# iNodeSwitch_v0_1.net
KiCad netlist of a schematic drawn in EAGLE
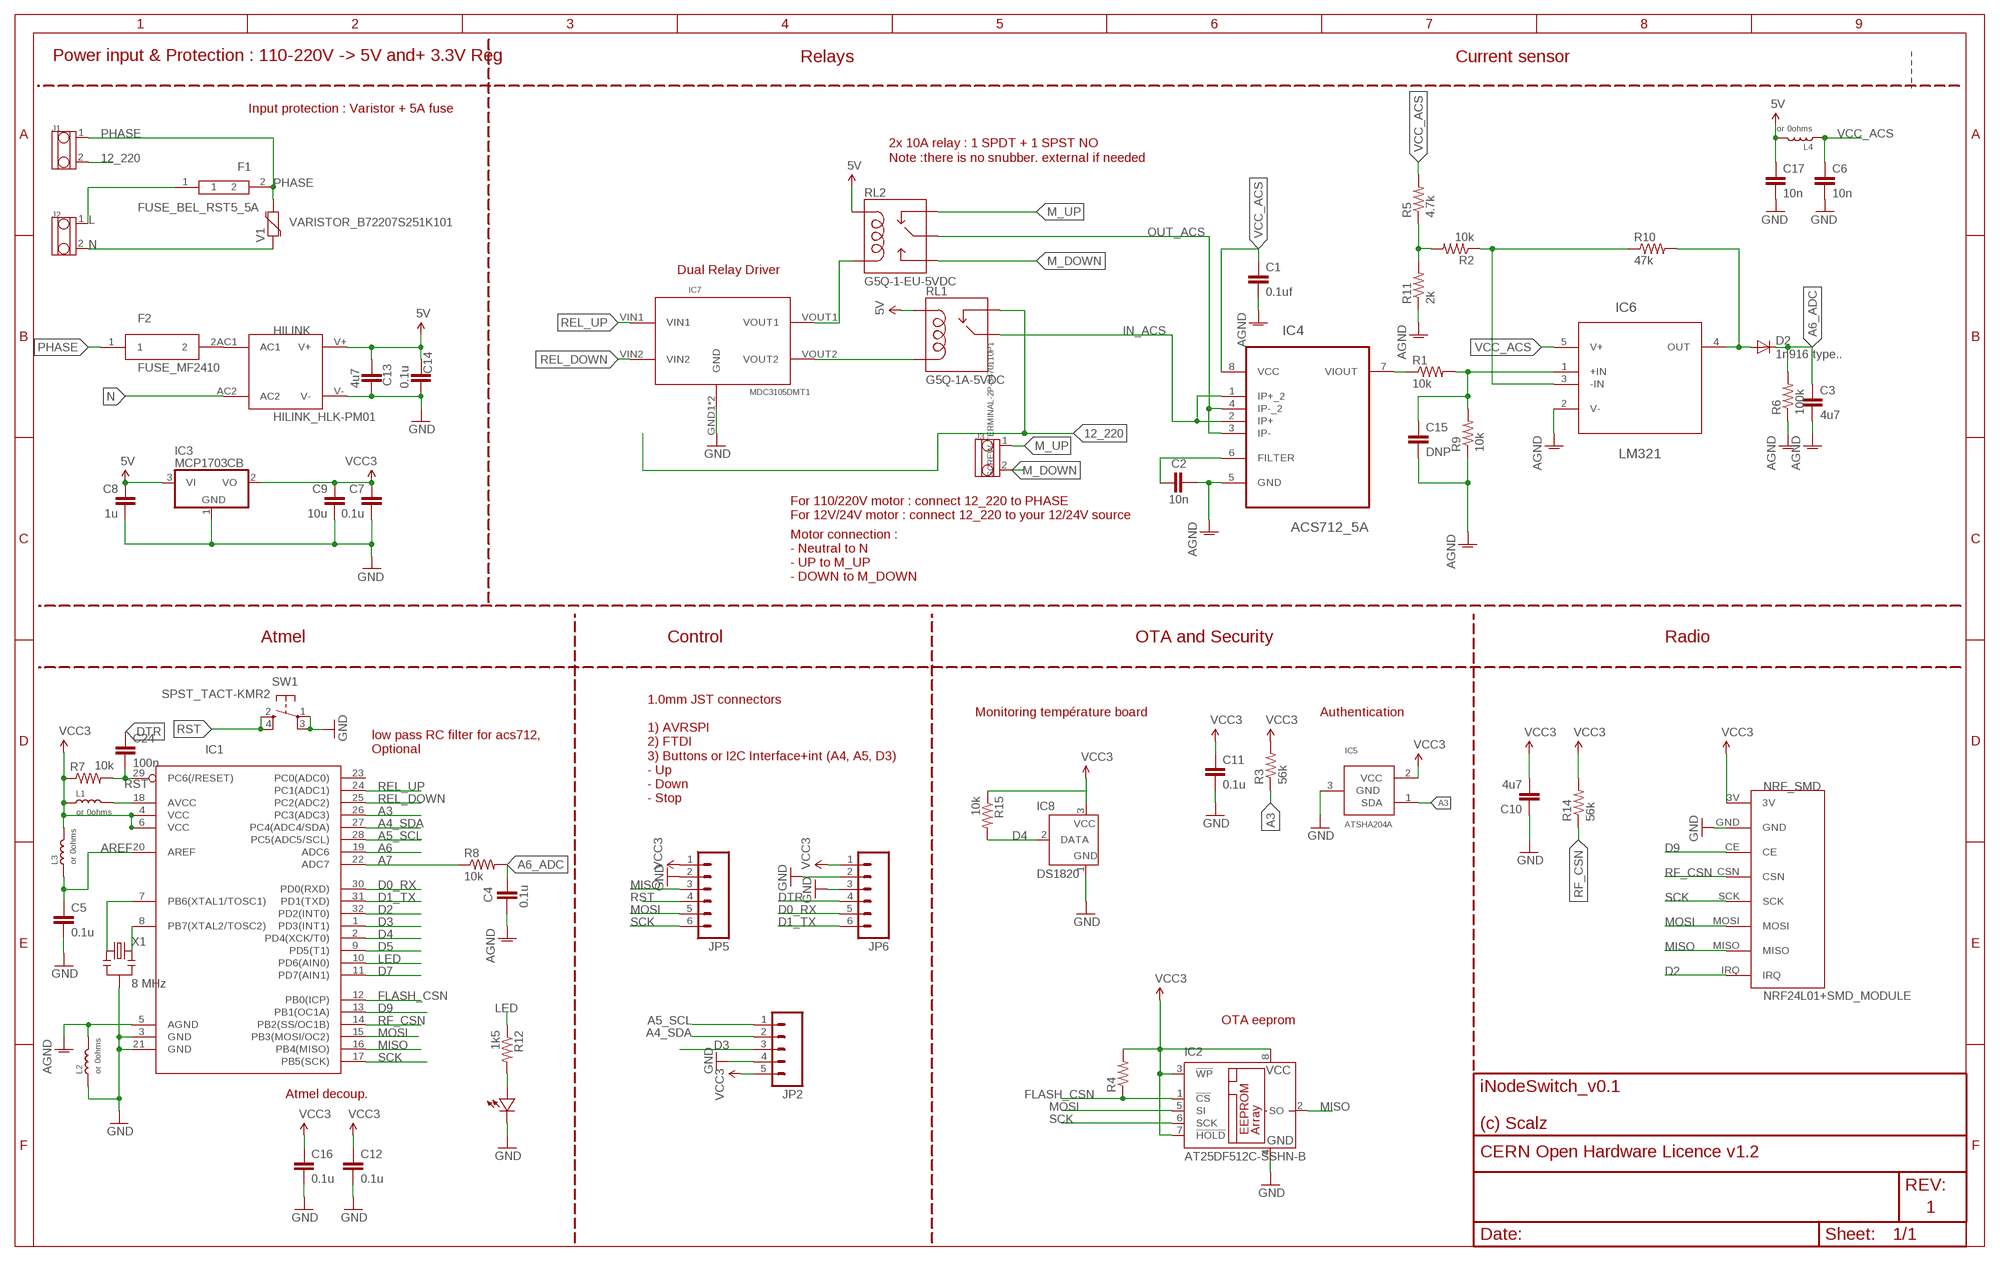
[diagram p0: schematic, sheet 1]

(export (version "E")
  (design (tool "Eeschema 10.0.6"))
  (components
    (comp (ref "C1")
      (value "0.1uf")
      (footprint "eagle-import:0805-CAP")
      (libsource (lib "eagle-import") (part "CAP0805-CAP"))
    )
    (comp (ref "C2")
      (value "10n")
      (footprint "eagle-import:0805-CAP")
      (libsource (lib "eagle-import") (part "CAP0805-CAP"))
    )
    (comp (ref "C3")
      (value "4u7")
      (footprint "eagle-import:0805-CAP")
      (libsource (lib "eagle-import") (part "CAP0805-CAP"))
    )
    (comp (ref "C4")
      (value "0.1u")
      (footprint "eagle-import:0805-CAP")
      (libsource (lib "eagle-import") (part "CAP0805-CAP"))
    )
    (comp (ref "C5")
      (value "0.1u")
      (footprint "eagle-import:0805-CAP")
      (libsource (lib "eagle-import") (part "CAP0805-CAP"))
    )
    (comp (ref "C6")
      (value "10n")
      (footprint "eagle-import:0805-CAP")
      (libsource (lib "eagle-import") (part "CAP0805-CAP"))
    )
    (comp (ref "C7")
      (value "0.1u")
      (footprint "eagle-import:0805-CAP")
      (libsource (lib "eagle-import") (part "CAP0805-CAP"))
    )
    (comp (ref "C8")
      (value "1u")
      (footprint "eagle-import:0805-CAP")
      (libsource (lib "eagle-import") (part "CAP0805-CAP"))
    )
    (comp (ref "C9")
      (value "10u")
      (footprint "eagle-import:0805-CAP")
      (libsource (lib "eagle-import") (part "CAP0805-CAP"))
    )
    (comp (ref "C10")
      (value "4u7")
      (footprint "eagle-import:0805-CAP")
      (libsource (lib "eagle-import") (part "CAP0805-CAP"))
    )
    (comp (ref "C11")
      (value "0.1u")
      (footprint "eagle-import:0805-CAP")
      (libsource (lib "eagle-import") (part "CAP0805-CAP"))
    )
    (comp (ref "C12")
      (value "0.1u")
      (footprint "eagle-import:0805-CAP")
      (libsource (lib "eagle-import") (part "CAP0805-CAP"))
    )
    (comp (ref "C13")
      (value "4u7")
      (footprint "eagle-import:0805-CAP")
      (libsource (lib "eagle-import") (part "CAP0805-CAP"))
    )
    (comp (ref "C14")
      (value "0.1u")
      (footprint "eagle-import:0805-CAP")
      (libsource (lib "eagle-import") (part "CAP0805-CAP"))
    )
    (comp (ref "C15")
      (value "DNP")
      (footprint "eagle-import:0805-CAP")
      (libsource (lib "eagle-import") (part "CAP0805-CAP"))
    )
    (comp (ref "C16")
      (value "0.1u")
      (footprint "eagle-import:0805-CAP")
      (libsource (lib "eagle-import") (part "CAP0805-CAP"))
    )
    (comp (ref "C17")
      (value "10n")
      (footprint "eagle-import:0805-CAP")
      (libsource (lib "eagle-import") (part "CAP0805-CAP"))
    )
    (comp (ref "C24")
      (value "100n")
      (footprint "eagle-import:0805-CAP")
      (libsource (lib "eagle-import") (part "CAP0805-CAP"))
    )
    (comp (ref "D1")
      (value "LED0805")
      (footprint "eagle-import:0805-LED")
      (libsource (lib "eagle-import") (part "LED0805"))
    )
    (comp (ref "D2")
      (value "1n916 type..")
      (footprint "eagle-import:SOD-323")
      (libsource (lib "eagle-import") (part "DIODESOD"))
    )
    (comp (ref "F1")
      (value "FUSE_BEL_RST5_5A")
      (footprint "eagle-import:FUSE_BEL_RST5_5A")
      (libsource (lib "eagle-import") (part "FUSE_BEL_RST5_5A"))
    )
    (comp (ref "F2")
      (value "FUSE_MF2410")
      (footprint "eagle-import:2410")
      (libsource (lib "eagle-import") (part "FUSE_MF2410"))
    )
    (comp (ref "HILINK")
      (value "HILINK_HLK-PM01")
      (footprint "eagle-import:HILINK_HLK-PM01")
      (libsource (lib "eagle-import") (part "HILINK_HLK-PM01"))
    )
    (comp (ref "IC1")
      (value "ATMega-328")
      (footprint "eagle-import:TQFP32-08")
      (libsource (lib "eagle-import") (part "ATMEGA168/328TQFP32"))
    )
    (comp (ref "IC2")
      (value "AT25DF512C-SSHN-B")
      (footprint "eagle-import:SO-08")
      (fields (field (name "MF") "MICROCHIP") (field (name "MPN") "25AA080/SN"))
      (libsource (lib "eagle-import") (part "25SNAA080"))
    )
    (comp (ref "IC3")
      (value "MCP1703CB")
      (footprint "eagle-import:SOT23")
      (libsource (lib "eagle-import") (part "MCP1703CB"))
    )
    (comp (ref "IC4")
      (value "ACS712_5A")
      (footprint "eagle-import:SOIC127P600X175-8N")
      (fields (field (name "MPN") "ACS712ELCTR-20A-T"))
      (libsource (lib "eagle-import") (part "ACS712ELCTR-20A-T"))
    )
    (comp (ref "IC5")
      (value "ATSHA204A")
      (footprint "eagle-import:SOT23")
      (libsource (lib "eagle-import") (part "ATSHA204A"))
    )
    (comp (ref "IC6")
      (value "LM321")
      (footprint "eagle-import:SOT95P285X120-5N")
      (fields (field (name "MPN") "LM321MF"))
      (libsource (lib "eagle-import") (part "LM321MF"))
    )
    (comp (ref "IC7")
      (value "MDC3105DMT1")
      (footprint "eagle-import:MDC3105DMT1")
      (libsource (lib "eagle-import") (part "MDC3105DMT1"))
    )
    (comp (ref "IC8")
      (value "DS1820")
      (footprint "eagle-import:TO92-")
      (libsource (lib "eagle-import") (part "DS1820"))
    )
    (comp (ref "J1")
      (value "SCREW-TERMINAL-2P-3470110P1")
      (footprint "eagle-import:2P-5.0")
      (libsource (lib "eagle-import") (part "SCREW-TERMINAL-2P-3470110P1"))
    )
    (comp (ref "J2")
      (value "SCREW-TERMINAL-2P-3470110P1")
      (footprint "eagle-import:2P-5.0")
      (libsource (lib "eagle-import") (part "SCREW-TERMINAL-2P-3470110P1"))
    )
    (comp (ref "J3")
      (value "SCREW-TERMINAL-2P-3470110P1")
      (footprint "eagle-import:2P-5.0")
      (libsource (lib "eagle-import") (part "SCREW-TERMINAL-2P-3470110P1"))
    )
    (comp (ref "JP2")
      (value "M05SMD")
      (footprint "eagle-import:1X05-1MM")
      (libsource (lib "eagle-import") (part "M05SMD"))
    )
    (comp (ref "JP5")
      (value "M06SMD-1MM")
      (footprint "eagle-import:1X06-1MM")
      (libsource (lib "eagle-import") (part "M06SMD-1MM"))
    )
    (comp (ref "JP6")
      (value "M06SMD-1MM")
      (footprint "eagle-import:1X06-1MM")
      (libsource (lib "eagle-import") (part "M06SMD-1MM"))
    )
    (comp (ref "L1")
      (value "or 0ohms")
      (footprint "eagle-import:L0805")
      (libsource (lib "eagle-import") (part "INDUCTOR/FERRITE-BEAD-0805"))
    )
    (comp (ref "L2")
      (value "or 0ohms")
      (footprint "eagle-import:L0805")
      (libsource (lib "eagle-import") (part "INDUCTOR/FERRITE-BEAD-0805"))
    )
    (comp (ref "L3")
      (value "or 0ohms")
      (footprint "eagle-import:L0805")
      (libsource (lib "eagle-import") (part "INDUCTOR/FERRITE-BEAD-0805"))
    )
    (comp (ref "L4")
      (value "or 0ohms")
      (footprint "eagle-import:L0805")
      (libsource (lib "eagle-import") (part "INDUCTOR/FERRITE-BEAD-0805"))
    )
    (comp (ref "NRF_SMD")
      (value "NRF24L01+SMD_MODULE")
      (footprint "eagle-import:NRF24L01+SMD_MODULE")
      (libsource (lib "eagle-import") (part "NRF24L01+SMD_MODULE"))
    )
    (comp (ref "R1")
      (value "10k")
      (footprint "eagle-import:0805-RES")
      (libsource (lib "eagle-import") (part "RESISTOR0805-RES"))
    )
    (comp (ref "R2")
      (value "10k")
      (footprint "eagle-import:0805-RES")
      (libsource (lib "eagle-import") (part "RESISTOR0805-RES"))
    )
    (comp (ref "R3")
      (value "56k")
      (footprint "eagle-import:0805-RES")
      (libsource (lib "eagle-import") (part "RESISTOR0805-RES"))
    )
    (comp (ref "R4")
      (value "RESISTOR0805-RES")
      (footprint "eagle-import:0805-RES")
      (libsource (lib "eagle-import") (part "RESISTOR0805-RES"))
    )
    (comp (ref "R5")
      (value "4.7k")
      (footprint "eagle-import:0805-RES")
      (libsource (lib "eagle-import") (part "RESISTOR0805-RES"))
    )
    (comp (ref "R6")
      (value "100k")
      (footprint "eagle-import:0805-RES")
      (libsource (lib "eagle-import") (part "RESISTOR0805-RES"))
    )
    (comp (ref "R7")
      (value "10k")
      (footprint "eagle-import:0805-RES")
      (libsource (lib "eagle-import") (part "RESISTOR0805-RES"))
    )
    (comp (ref "R8")
      (value "10k")
      (footprint "eagle-import:0805-RES")
      (libsource (lib "eagle-import") (part "RESISTOR0805-RES"))
    )
    (comp (ref "R9")
      (value "10k")
      (footprint "eagle-import:0805-RES")
      (libsource (lib "eagle-import") (part "RESISTOR0805-RES"))
    )
    (comp (ref "R10")
      (value "47k")
      (footprint "eagle-import:0805-RES")
      (libsource (lib "eagle-import") (part "RESISTOR0805-RES"))
    )
    (comp (ref "R11")
      (value "2k")
      (footprint "eagle-import:0805-RES")
      (libsource (lib "eagle-import") (part "RESISTOR0805-RES"))
    )
    (comp (ref "R12")
      (value "1k5")
      (footprint "eagle-import:0805-RES")
      (libsource (lib "eagle-import") (part "RESISTOR0805-RES"))
    )
    (comp (ref "R14")
      (value "56k")
      (footprint "eagle-import:0805-RES")
      (libsource (lib "eagle-import") (part "RESISTOR0805-RES"))
    )
    (comp (ref "R15")
      (value "10k")
      (footprint "eagle-import:0805-RES")
      (libsource (lib "eagle-import") (part "RESISTOR0805-RES"))
    )
    (comp (ref "RL1")
      (value "G5Q-1A-5VDC")
      (footprint "eagle-import:G5Q_SINGLE")
      (libsource (lib "eagle-import") (part "G5Q_SINGLE"))
    )
    (comp (ref "RL2")
      (value "G5Q-1-EU-5VDC")
      (footprint "eagle-import:RELAY-G5Q")
      (libsource (lib "eagle-import") (part "RELAYPTH"))
    )
    (comp (ref "SW1")
      (value "SPST_TACT-KMR2")
      (footprint "eagle-import:KMR2")
      (libsource (lib "eagle-import") (part "SPST_TACT-KMR2"))
    )
    (comp (ref "V1")
      (value "VARISTOR_B72207S251K101")
      (footprint "eagle-import:VARISTOR_B72207S251K101")
      (libsource (lib "eagle-import") (part "VARISTOR_B72207S251K101"))
    )
    (comp (ref "X1")
      (value "8 MHz")
      (footprint "eagle-import:RESONATOR-SMD")
      (libsource (lib "eagle-import") (part "RESONATORSMD"))
    )
  )
  (nets
    (net (code "1") (name "/A4_SDA") (class "Default")
      (node (ref "IC1") (pin "27") (pinfunction "PC4(ADC4/SDA)_27") (pintype "bidirectional"))
      (node (ref "JP2") (pin "2") (pinfunction "2_2") (pintype "passive"))
    )
    (net (code "2") (name "/A5_SCL") (class "Default")
      (node (ref "IC1") (pin "28") (pinfunction "PC5(ADC5/SCL)_28") (pintype "bidirectional"))
      (node (ref "JP2") (pin "1") (pinfunction "1_1") (pintype "passive"))
    )
    (net (code "3") (name "/A6") (class "Default")
      (node (ref "IC1") (pin "19") (pinfunction "ADC6_19") (pintype "bidirectional"))
    )
    (net (code "4") (name "/A7") (class "Default")
      (node (ref "IC1") (pin "22") (pinfunction "ADC7_22") (pintype "bidirectional"))
      (node (ref "R8") (pin "1") (pinfunction "1_1") (pintype "passive"))
    )
    (net (code "5") (name "/AREF") (class "Default")
      (node (ref "C5") (pin "1") (pinfunction "1_1") (pintype "passive"))
      (node (ref "IC1") (pin "20") (pinfunction "AREF_20") (pintype "bidirectional"))
      (node (ref "L3") (pin "1") (pinfunction "1_1") (pintype "passive"))
    )
    (net (code "6") (name "/D0_RX") (class "Default")
      (node (ref "IC1") (pin "30") (pinfunction "PD0(RXD)_30") (pintype "bidirectional"))
      (node (ref "JP6") (pin "5") (pinfunction "5_5") (pintype "passive"))
    )
    (net (code "7") (name "/D1_TX") (class "Default")
      (node (ref "IC1") (pin "31") (pinfunction "PD1(TXD)_31") (pintype "bidirectional"))
      (node (ref "JP6") (pin "6") (pinfunction "6_6") (pintype "passive"))
    )
    (net (code "8") (name "/D2") (class "Default")
      (node (ref "IC1") (pin "32") (pinfunction "PD2(INT0)_32") (pintype "bidirectional"))
      (node (ref "NRF_SMD") (pin "IRQ") (pinfunction "IRQ_IRQ") (pintype "bidirectional"))
    )
    (net (code "9") (name "/D3") (class "Default")
      (node (ref "IC1") (pin "1") (pinfunction "PD3(INT1)_1") (pintype "bidirectional"))
      (node (ref "JP2") (pin "3") (pinfunction "3_3") (pintype "passive"))
    )
    (net (code "10") (name "/D4") (class "Default")
      (node (ref "IC1") (pin "2") (pinfunction "PD4(XCK/T0)_2") (pintype "bidirectional"))
      (node (ref "IC8") (pin "2") (pinfunction "DATA_2") (pintype "input"))
      (node (ref "R15") (pin "2") (pinfunction "2_2") (pintype "passive"))
    )
    (net (code "11") (name "/D5") (class "Default")
      (node (ref "IC1") (pin "9") (pinfunction "PD5(T1)_9") (pintype "bidirectional"))
    )
    (net (code "12") (name "/D7") (class "Default")
      (node (ref "IC1") (pin "11") (pinfunction "PD7(AIN1)_11") (pintype "bidirectional"))
    )
    (net (code "13") (name "/D9") (class "Default")
      (node (ref "IC1") (pin "13") (pinfunction "PB1(OC1A)_13") (pintype "bidirectional"))
      (node (ref "NRF_SMD") (pin "CE") (pinfunction "CE_CE") (pintype "bidirectional"))
    )
    (net (code "14") (name "/FLASH_CSN") (class "Default")
      (node (ref "IC1") (pin "12") (pinfunction "PB0(ICP)_12") (pintype "bidirectional"))
      (node (ref "IC2") (pin "1") (pinfunction "~{CS}_1") (pintype "input"))
      (node (ref "R4") (pin "1") (pinfunction "1_1") (pintype "passive"))
    )
    (net (code "15") (name "/IN_ACS") (class "Default")
      (node (ref "IC4") (pin "1") (pinfunction "IP+_2_1") (pintype "input"))
      (node (ref "IC4") (pin "2") (pinfunction "IP+_2") (pintype "input"))
      (node (ref "RL1") (pin "2") (pinfunction "MAIN_2") (pintype "bidirectional"))
    )
    (net (code "16") (name "/L") (class "Default")
      (node (ref "F1") (pin "1") (pinfunction "1_1") (pintype "bidirectional"))
      (node (ref "J2") (pin "1") (pinfunction "1_1") (pintype "bidirectional"))
    )
    (net (code "17") (name "/LED") (class "Default")
      (node (ref "IC1") (pin "10") (pinfunction "PD6(AIN0)_10") (pintype "bidirectional"))
      (node (ref "R12") (pin "1") (pinfunction "1_1") (pintype "passive"))
    )
    (net (code "18") (name "/MISO") (class "Default")
      (node (ref "IC1") (pin "16") (pinfunction "PB4(MISO)_16") (pintype "bidirectional"))
      (node (ref "IC2") (pin "2") (pinfunction "SO_2") (pintype "bidirectional"))
      (node (ref "JP5") (pin "3") (pinfunction "3_3") (pintype "passive"))
      (node (ref "NRF_SMD") (pin "MISO") (pinfunction "MISO_MISO") (pintype "bidirectional"))
    )
    (net (code "19") (name "/MOSI") (class "Default")
      (node (ref "IC1") (pin "15") (pinfunction "PB3(MOSI/OC2)_15") (pintype "bidirectional"))
      (node (ref "IC2") (pin "5") (pinfunction "SI_5") (pintype "input"))
      (node (ref "JP5") (pin "5") (pinfunction "5_5") (pintype "passive"))
      (node (ref "NRF_SMD") (pin "MOSI") (pinfunction "MOSI_MOSI") (pintype "bidirectional"))
    )
    (net (code "20") (name "/OUT_ACS") (class "Default")
      (node (ref "IC4") (pin "3") (pinfunction "IP-_3") (pintype "input"))
      (node (ref "IC4") (pin "4") (pinfunction "IP-_2_4") (pintype "input"))
      (node (ref "RL2") (pin "2") (pinfunction "MAIN_2") (pintype "bidirectional"))
    )
    (net (code "21") (name "/SCK") (class "Default")
      (node (ref "IC1") (pin "17") (pinfunction "PB5(SCK)_17") (pintype "bidirectional"))
      (node (ref "IC2") (pin "6") (pinfunction "SCK_6") (pintype "input"))
      (node (ref "JP5") (pin "6") (pinfunction "6_6") (pintype "passive"))
      (node (ref "NRF_SMD") (pin "SCK") (pinfunction "SCK_SCK") (pintype "bidirectional"))
    )
    (net (code "22") (name "5V") (class "Default")
      (node (ref "C13") (pin "1") (pinfunction "1_1") (pintype "passive"))
      (node (ref "C14") (pin "1") (pinfunction "1_1") (pintype "passive"))
      (node (ref "C17") (pin "1") (pinfunction "1_1") (pintype "passive"))
      (node (ref "C8") (pin "1") (pinfunction "1_1") (pintype "passive"))
      (node (ref "HILINK") (pin "V+") (pinfunction "V+_V+") (pintype "bidirectional"))
      (node (ref "IC3") (pin "3") (pinfunction "VI_3") (pintype "input"))
      (node (ref "L4") (pin "2") (pinfunction "2_2") (pintype "passive"))
      (node (ref "RL1") (pin "1") (pinfunction "COIL1_1") (pintype "bidirectional"))
      (node (ref "RL2") (pin "5") (pinfunction "COIL1_5") (pintype "bidirectional"))
    )
    (net (code "23") (name "12_220") (class "Default")
      (node (ref "J1") (pin "2") (pinfunction "2_2") (pintype "bidirectional"))
      (node (ref "RL1") (pin "3") (pinfunction "NC_3") (pintype "bidirectional"))
    )
    (net (code "24") (name "A3") (class "Default")
      (node (ref "IC1") (pin "26") (pinfunction "PC3(ADC3)_26") (pintype "bidirectional"))
      (node (ref "IC5") (pin "1") (pinfunction "SDA_1") (pintype "bidirectional"))
      (node (ref "R3") (pin "1") (pinfunction "1_1") (pintype "passive"))
    )
    (net (code "25") (name "A6_ADC") (class "Default")
      (node (ref "C3") (pin "1") (pinfunction "1_1") (pintype "passive"))
      (node (ref "C4") (pin "2") (pinfunction "2_2") (pintype "passive"))
      (node (ref "D2") (pin "1") (pinfunction "C_1") (pintype "passive"))
      (node (ref "R6") (pin "2") (pinfunction "2_2") (pintype "passive"))
      (node (ref "R8") (pin "2") (pinfunction "2_2") (pintype "passive"))
    )
    (net (code "26") (name "AGND") (class "Default")
      (node (ref "C1") (pin "2") (pinfunction "2_2") (pintype "passive"))
      (node (ref "C15") (pin "2") (pinfunction "2_2") (pintype "passive"))
      (node (ref "C2") (pin "2") (pinfunction "2_2") (pintype "passive"))
      (node (ref "C3") (pin "2") (pinfunction "2_2") (pintype "passive"))
      (node (ref "C4") (pin "1") (pinfunction "1_1") (pintype "passive"))
      (node (ref "IC1") (pin "5") (pinfunction "AGND_5") (pintype "bidirectional"))
      (node (ref "IC4") (pin "5") (pinfunction "GND_5") (pintype "passive"))
      (node (ref "IC6") (pin "2") (pinfunction "V-_2") (pintype "power_in"))
      (node (ref "L2") (pin "2") (pinfunction "2_2") (pintype "passive"))
      (node (ref "R11") (pin "1") (pinfunction "1_1") (pintype "passive"))
      (node (ref "R6") (pin "1") (pinfunction "1_1") (pintype "passive"))
      (node (ref "R9") (pin "1") (pinfunction "1_1") (pintype "passive"))
    )
    (net (code "27") (name "DTR") (class "Default")
      (node (ref "C24") (pin "1") (pinfunction "1_1") (pintype "passive"))
      (node (ref "JP6") (pin "4") (pinfunction "4_4") (pintype "passive"))
    )
    (net (code "28") (name "GND") (class "Default")
      (node (ref "C10") (pin "1") (pinfunction "1_1") (pintype "passive"))
      (node (ref "C11") (pin "2") (pinfunction "2_2") (pintype "passive"))
      (node (ref "C12") (pin "2") (pinfunction "2_2") (pintype "passive"))
      (node (ref "C13") (pin "2") (pinfunction "2_2") (pintype "passive"))
      (node (ref "C14") (pin "2") (pinfunction "2_2") (pintype "passive"))
      (node (ref "C16") (pin "2") (pinfunction "2_2") (pintype "passive"))
      (node (ref "C17") (pin "2") (pinfunction "2_2") (pintype "passive"))
      (node (ref "C5") (pin "2") (pinfunction "2_2") (pintype "passive"))
      (node (ref "C6") (pin "2") (pinfunction "2_2") (pintype "passive"))
      (node (ref "C7") (pin "2") (pinfunction "2_2") (pintype "passive"))
      (node (ref "C8") (pin "2") (pinfunction "2_2") (pintype "passive"))
      (node (ref "C9") (pin "2") (pinfunction "2_2") (pintype "passive"))
      (node (ref "D1") (pin "MINUS") (pinfunction "MINUS_MINUS") (pintype "passive"))
      (node (ref "HILINK") (pin "V-") (pinfunction "V-_V-") (pintype "bidirectional"))
      (node (ref "IC1") (pin "21") (pinfunction "GND_21") (pintype "bidirectional"))
      (node (ref "IC1") (pin "3") (pinfunction "GND_3") (pintype "bidirectional"))
      (node (ref "IC2") (pin "4") (pinfunction "GND_4") (pintype "power_in"))
      (node (ref "IC3") (pin "1") (pinfunction "GND_1") (pintype "passive"))
      (node (ref "IC5") (pin "3") (pinfunction "GND_3") (pintype "bidirectional"))
      (node (ref "IC7") (pin "GND1") (pinfunction "GND_GND1") (pintype "bidirectional"))
      (node (ref "IC7") (pin "GND2") (pinfunction "GND_GND2") (pintype "bidirectional"))
      (node (ref "IC8") (pin "1") (pinfunction "GND_1") (pintype "passive"))
      (node (ref "JP2") (pin "4") (pinfunction "4_4") (pintype "passive"))
      (node (ref "JP5") (pin "2") (pinfunction "2_2") (pintype "passive"))
      (node (ref "JP6") (pin "2") (pinfunction "2_2") (pintype "passive"))
      (node (ref "JP6") (pin "3") (pinfunction "3_3") (pintype "passive"))
      (node (ref "L2") (pin "1") (pinfunction "1_1") (pintype "passive"))
      (node (ref "NRF_SMD") (pin "GND") (pinfunction "GND_GND") (pintype "bidirectional"))
      (node (ref "SW1") (pin "1") (pinfunction "P_1") (pintype "passive"))
      (node (ref "SW1") (pin "3") (pinfunction "P1_3") (pintype "passive"))
      (node (ref "X1") (pin "2") (pinfunction "2_2") (pintype "passive"))
    )
    (net (code "29") (name "M_DOWN") (class "Default")
      (node (ref "J3") (pin "2") (pinfunction "2_2") (pintype "bidirectional"))
      (node (ref "RL2") (pin "3") (pinfunction "NO_3") (pintype "bidirectional"))
    )
    (net (code "30") (name "M_UP") (class "Default")
      (node (ref "J3") (pin "1") (pinfunction "1_1") (pintype "bidirectional"))
      (node (ref "RL2") (pin "4") (pinfunction "NC_4") (pintype "bidirectional"))
    )
    (net (code "31") (name "N") (class "Default")
      (node (ref "HILINK") (pin "AC2") (pinfunction "AC2_AC2") (pintype "bidirectional"))
      (node (ref "J2") (pin "2") (pinfunction "2_2") (pintype "bidirectional"))
      (node (ref "V1") (pin "1") (pinfunction "1_1") (pintype "passive"))
    )
    (net (code "32") (name "Net-(D1-PadPLUS)") (class "Default")
      (node (ref "D1") (pin "PLUS") (pinfunction "PLUS_PLUS") (pintype "passive"))
      (node (ref "R12") (pin "2") (pinfunction "2_2") (pintype "passive"))
    )
    (net (code "33") (name "Net-(D2-A)") (class "Default")
      (node (ref "D2") (pin "2") (pinfunction "A_2") (pintype "passive"))
      (node (ref "IC6") (pin "4") (pinfunction "OUT_4") (pintype "output"))
      (node (ref "R10") (pin "2") (pinfunction "2_2") (pintype "passive"))
    )
    (net (code "34") (name "Net-(F2-Pad2)") (class "Default")
      (node (ref "F2") (pin "2") (pinfunction "2_2") (pintype "bidirectional"))
      (node (ref "HILINK") (pin "AC1") (pinfunction "AC1_AC1") (pintype "bidirectional"))
    )
    (net (code "35") (name "Net-(IC1-AVCC)") (class "Default")
      (node (ref "IC1") (pin "18") (pinfunction "AVCC_18") (pintype "bidirectional"))
      (node (ref "L1") (pin "2") (pinfunction "2_2") (pintype "passive"))
    )
    (net (code "36") (name "Net-(IC1-PB6(XTAL1{slash}TOSC1))") (class "Default")
      (node (ref "IC1") (pin "7") (pinfunction "PB6(XTAL1/TOSC1)_7") (pintype "bidirectional"))
      (node (ref "X1") (pin "1") (pinfunction "1_1") (pintype "passive"))
    )
    (net (code "37") (name "Net-(IC1-PB7(XTAL2{slash}TOSC2))") (class "Default")
      (node (ref "IC1") (pin "8") (pinfunction "PB7(XTAL2/TOSC2)_8") (pintype "bidirectional"))
      (node (ref "X1") (pin "3") (pinfunction "3_3") (pintype "passive"))
    )
    (net (code "38") (name "Net-(IC4-FILTER)") (class "Default")
      (node (ref "C2") (pin "1") (pinfunction "1_1") (pintype "passive"))
      (node (ref "IC4") (pin "6") (pinfunction "FILTER_6") (pintype "input"))
    )
    (net (code "39") (name "Net-(IC4-VIOUT)") (class "Default")
      (node (ref "IC4") (pin "7") (pinfunction "VIOUT_7") (pintype "output"))
      (node (ref "R1") (pin "1") (pinfunction "1_1") (pintype "passive"))
    )
    (net (code "40") (name "Net-(IC6-+IN)") (class "Default")
      (node (ref "C15") (pin "1") (pinfunction "1_1") (pintype "passive"))
      (node (ref "IC6") (pin "1") (pinfunction "+IN_1") (pintype "input"))
      (node (ref "R1") (pin "2") (pinfunction "2_2") (pintype "passive"))
      (node (ref "R9") (pin "2") (pinfunction "2_2") (pintype "passive"))
    )
    (net (code "41") (name "Net-(IC6--IN)") (class "Default")
      (node (ref "IC6") (pin "3") (pinfunction "-IN_3") (pintype "input"))
      (node (ref "R10") (pin "1") (pinfunction "1_1") (pintype "passive"))
      (node (ref "R2") (pin "1") (pinfunction "1_1") (pintype "passive"))
    )
    (net (code "42") (name "Net-(R11-Pad2)") (class "Default")
      (node (ref "R11") (pin "2") (pinfunction "2_2") (pintype "passive"))
      (node (ref "R2") (pin "2") (pinfunction "2_2") (pintype "passive"))
      (node (ref "R5") (pin "1") (pinfunction "1_1") (pintype "passive"))
    )
    (net (code "43") (name "Net-(RL1-COIL2)") (class "Default")
      (node (ref "IC7") (pin "VOUT2") (pinfunction "VOUT2_VOUT2") (pintype "bidirectional"))
      (node (ref "RL1") (pin "5") (pinfunction "COIL2_5") (pintype "bidirectional"))
    )
    (net (code "44") (name "Net-(RL2-COIL2)") (class "Default")
      (node (ref "IC7") (pin "VOUT1") (pinfunction "VOUT1_VOUT1") (pintype "bidirectional"))
      (node (ref "RL2") (pin "1") (pinfunction "COIL2_1") (pintype "bidirectional"))
    )
    (net (code "45") (name "PHASE") (class "Default")
      (node (ref "F1") (pin "2") (pinfunction "2_2") (pintype "bidirectional"))
      (node (ref "F2") (pin "1") (pinfunction "1_1") (pintype "bidirectional"))
      (node (ref "J1") (pin "1") (pinfunction "1_1") (pintype "bidirectional"))
      (node (ref "V1") (pin "2") (pinfunction "2_2") (pintype "passive"))
    )
    (net (code "46") (name "REL_DOWN") (class "Default")
      (node (ref "IC1") (pin "25") (pinfunction "PC2(ADC2)_25") (pintype "bidirectional"))
      (node (ref "IC7") (pin "VIN2") (pinfunction "VIN2_VIN2") (pintype "bidirectional"))
    )
    (net (code "47") (name "REL_UP") (class "Default")
      (node (ref "IC1") (pin "24") (pinfunction "PC1(ADC1)_24") (pintype "bidirectional"))
      (node (ref "IC7") (pin "VIN1") (pinfunction "VIN1_VIN1") (pintype "bidirectional"))
    )
    (net (code "48") (name "RF_CSN") (class "Default")
      (node (ref "IC1") (pin "14") (pinfunction "PB2(SS/OC1B)_14") (pintype "bidirectional"))
      (node (ref "R14") (pin "1") (pinfunction "1_1") (pintype "passive"))
    )
    (net (code "49") (name "RST") (class "Default")
      (node (ref "C24") (pin "2") (pinfunction "2_2") (pintype "passive"))
      (node (ref "IC1") (pin "29") (pinfunction "PC6(/RESET)_29") (pintype "bidirectional"))
      (node (ref "JP5") (pin "4") (pinfunction "4_4") (pintype "passive"))
      (node (ref "R7") (pin "2") (pinfunction "2_2") (pintype "passive"))
      (node (ref "SW1") (pin "2") (pinfunction "S_2") (pintype "passive"))
      (node (ref "SW1") (pin "4") (pinfunction "S1_4") (pintype "passive"))
    )
    (net (code "50") (name "VCC3") (class "Default")
      (node (ref "C10") (pin "2") (pinfunction "2_2") (pintype "passive"))
      (node (ref "C11") (pin "1") (pinfunction "1_1") (pintype "passive"))
      (node (ref "C12") (pin "1") (pinfunction "1_1") (pintype "passive"))
      (node (ref "C16") (pin "1") (pinfunction "1_1") (pintype "passive"))
      (node (ref "C7") (pin "1") (pinfunction "1_1") (pintype "passive"))
      (node (ref "C9") (pin "1") (pinfunction "1_1") (pintype "passive"))
      (node (ref "IC1") (pin "4") (pinfunction "VCC_4") (pintype "bidirectional"))
      (node (ref "IC1") (pin "6") (pinfunction "VCC_6") (pintype "bidirectional"))
      (node (ref "IC2") (pin "3") (pinfunction "~{WP}_3") (pintype "input"))
      (node (ref "IC2") (pin "7") (pinfunction "~{HOLD}_7") (pintype "input"))
      (node (ref "IC2") (pin "8") (pinfunction "VCC_8") (pintype "power_in"))
      (node (ref "IC3") (pin "2") (pinfunction "VO_2") (pintype "passive"))
      (node (ref "IC5") (pin "2") (pinfunction "VCC_2") (pintype "bidirectional"))
      (node (ref "IC8") (pin "3") (pinfunction "VCC_3") (pintype "passive"))
      (node (ref "JP2") (pin "5") (pinfunction "5_5") (pintype "passive"))
      (node (ref "JP5") (pin "1") (pinfunction "1_1") (pintype "passive"))
      (node (ref "JP6") (pin "1") (pinfunction "1_1") (pintype "passive"))
      (node (ref "L1") (pin "1") (pinfunction "1_1") (pintype "passive"))
      (node (ref "L3") (pin "2") (pinfunction "2_2") (pintype "passive"))
      (node (ref "NRF_SMD") (pin "3V") (pinfunction "3V_3V") (pintype "bidirectional"))
      (node (ref "R14") (pin "2") (pinfunction "2_2") (pintype "passive"))
      (node (ref "R15") (pin "1") (pinfunction "1_1") (pintype "passive"))
      (node (ref "R3") (pin "2") (pinfunction "2_2") (pintype "passive"))
      (node (ref "R4") (pin "2") (pinfunction "2_2") (pintype "passive"))
      (node (ref "R7") (pin "1") (pinfunction "1_1") (pintype "passive"))
    )
    (net (code "51") (name "VCC_ACS") (class "Default")
      (node (ref "C1") (pin "1") (pinfunction "1_1") (pintype "passive"))
      (node (ref "C6") (pin "1") (pinfunction "1_1") (pintype "passive"))
      (node (ref "IC4") (pin "8") (pinfunction "VCC_8") (pintype "power_in"))
      (node (ref "IC6") (pin "5") (pinfunction "V+_5") (pintype "power_in"))
      (node (ref "L4") (pin "1") (pinfunction "1_1") (pintype "passive"))
      (node (ref "R5") (pin "2") (pinfunction "2_2") (pintype "passive"))
    )
    (net (code "52") (name "unconnected-(IC1-PC0(ADC0)-Pad23)") (class "Default")
      (node (ref "IC1") (pin "23") (pinfunction "PC0(ADC0)_23") (pintype "bidirectional"))
    )
    (net (code "53") (name "unconnected-(NRF_SMD-PadCSN)") (class "Default")
      (node (ref "NRF_SMD") (pin "CSN") (pinfunction "CSN_CSN") (pintype "bidirectional"))
    )
  )
)
